# Sheet1.net
KiCad netlist of a schematic drawn in Altium Designer
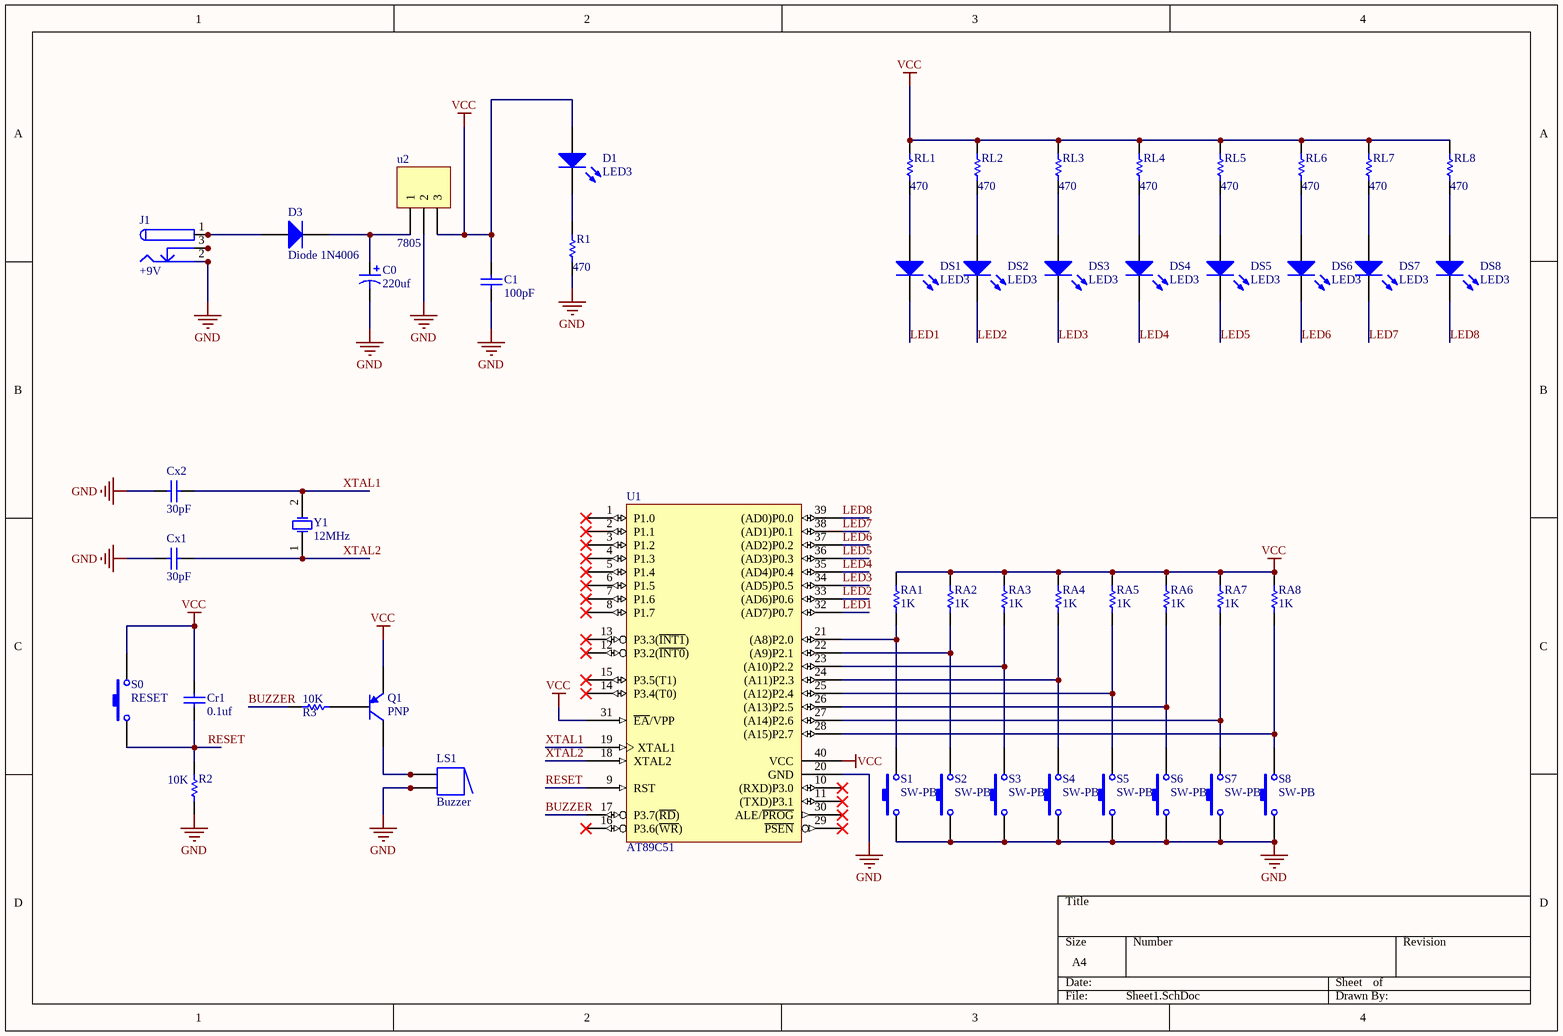
[diagram p0: Sheet1.SchDoc]

(export (version "E")
  (design (tool "Eeschema 10.0.6"))
  (components
    (comp (ref "C0")
      (value "220uf")
      (footprint "RB7.6-15")
      (description "Polarized Capacitor (Radial)")
      (fields (field (name "Comment") "Cap Pol1") (field (name "PUBLISHER") "Altium Limited"))
      (libsource (lib "Chap-11-实践题(3)") (part "Cap Pol1"))
    )
    (comp (ref "C1")
      (value "100pF")
      (footprint "RAD-0.3")
      (description "Capacitor")
      (fields (field (name "Comment") "Cap") (field (name "PUBLISHER") "Altium Limited"))
      (libsource (lib "Chap-11-实践题(3)") (part "Cap"))
    )
    (comp (ref "Cr1")
      (value "0.1uf")
      (footprint "RAD-0.3")
      (description "Capacitor")
      (fields (field (name "Comment") "Cap") (field (name "PUBLISHER") "Altium Limited"))
      (libsource (lib "Chap-11-实践题(3)") (part "Cap"))
    )
    (comp (ref "Cx1")
      (value "30pF")
      (footprint "RAD-0.3")
      (description "Capacitor")
      (fields (field (name "Comment") "Cap") (field (name "PUBLISHER") "Altium Limited"))
      (libsource (lib "Chap-11-实践题(3)") (part "Cap"))
    )
    (comp (ref "Cx2")
      (value "30pF")
      (footprint "RAD-0.3")
      (description "Capacitor")
      (fields (field (name "Comment") "Cap") (field (name "PUBLISHER") "Altium Limited"))
      (libsource (lib "Chap-11-实践题(3)") (part "Cap"))
    )
    (comp (ref "D1")
      (value "LED3")
      (footprint "3.5X2.8X1.9")
      (description "Typical BLUE SiC LED")
      (fields (field (name "PUBLISHER") "Altium Limited"))
      (libsource (lib "Chap-11-实践题(3)") (part "LED3"))
    )
    (comp (ref "D3")
      (value "Diode 1N4006")
      (footprint "DO-41")
      (description "1 Amp General Purpose Rectifier")
      (fields (field (name "PUBLISHER") "Altium Limited"))
      (libsource (lib "Chap-11-实践题(3)") (part "Diode 1N4006"))
    )
    (comp (ref "DS1")
      (value "LED3")
      (footprint "3.5X2.8X1.9")
      (description "Typical BLUE SiC LED")
      (fields (field (name "PUBLISHER") "Altium Limited"))
      (libsource (lib "Chap-11-实践题(3)") (part "LED3"))
    )
    (comp (ref "DS2")
      (value "LED3")
      (footprint "3.5X2.8X1.9")
      (description "Typical BLUE SiC LED")
      (fields (field (name "PUBLISHER") "Altium Limited"))
      (libsource (lib "Chap-11-实践题(3)") (part "LED3"))
    )
    (comp (ref "DS3")
      (value "LED3")
      (footprint "3.5X2.8X1.9")
      (description "Typical BLUE SiC LED")
      (fields (field (name "PUBLISHER") "Altium Limited"))
      (libsource (lib "Chap-11-实践题(3)") (part "LED3"))
    )
    (comp (ref "DS4")
      (value "LED3")
      (footprint "3.5X2.8X1.9")
      (description "Typical BLUE SiC LED")
      (fields (field (name "PUBLISHER") "Altium Limited"))
      (libsource (lib "Chap-11-实践题(3)") (part "LED3"))
    )
    (comp (ref "DS5")
      (value "LED3")
      (footprint "3.5X2.8X1.9")
      (description "Typical BLUE SiC LED")
      (fields (field (name "PUBLISHER") "Altium Limited"))
      (libsource (lib "Chap-11-实践题(3)") (part "LED3"))
    )
    (comp (ref "DS6")
      (value "LED3")
      (footprint "3.5X2.8X1.9")
      (description "Typical BLUE SiC LED")
      (fields (field (name "PUBLISHER") "Altium Limited"))
      (libsource (lib "Chap-11-实践题(3)") (part "LED3"))
    )
    (comp (ref "DS7")
      (value "LED3")
      (footprint "3.5X2.8X1.9")
      (description "Typical BLUE SiC LED")
      (fields (field (name "PUBLISHER") "Altium Limited"))
      (libsource (lib "Chap-11-实践题(3)") (part "LED3"))
    )
    (comp (ref "DS8")
      (value "LED3")
      (footprint "3.5X2.8X1.9")
      (description "Typical BLUE SiC LED")
      (fields (field (name "PUBLISHER") "Altium Limited"))
      (libsource (lib "Chap-11-实践题(3)") (part "LED3"))
    )
    (comp (ref "J1")
      (value "+9V")
      (footprint "KLD-0202")
      (description "Low Voltage Power Supply Connector")
      (fields (field (name "PUBLISHER") "Altium Limited"))
      (libsource (lib "Chap-11-实践题(3)") (part "PWR2.5"))
    )
    (comp (ref "LS1")
      (value "Buzzer")
      (footprint "ABSM-1574")
      (description "Magnetic Transducer Buzzer")
      (fields (field (name "PUBLISHER") "Altium Limited"))
      (libsource (lib "Chap-11-实践题(3)") (part "Buzzer"))
    )
    (comp (ref "Q1")
      (value "PNP")
      (footprint "TO-92A")
      (description "PNP General Purpose Amplifier")
      (fields (field (name "PUBLISHER") "Altium Limited"))
      (libsource (lib "Chap-11-实践题(3)") (part "2N3906"))
    )
    (comp (ref "R1")
      (value "470")
      (footprint "AXIAL-0.3")
      (description "Resistor")
      (fields (field (name "Comment") "Res1") (field (name "PUBLISHER") "Altium Limited"))
      (libsource (lib "Chap-11-实践题(3)") (part "Res1"))
    )
    (comp (ref "R2")
      (value "10K")
      (footprint "AXIAL-0.3")
      (description "Resistor")
      (fields (field (name "Comment") "Res1") (field (name "PUBLISHER") "Altium Limited"))
      (libsource (lib "Chap-11-实践题(3)") (part "Res1"))
    )
    (comp (ref "R3")
      (value "10K")
      (footprint "AXIAL-0.3")
      (description "Resistor")
      (fields (field (name "Comment") "Res1") (field (name "PUBLISHER") "Altium Limited"))
      (libsource (lib "Chap-11-实践题(3)") (part "Res1"))
    )
    (comp (ref "RA1")
      (value "1K")
      (footprint "AXIAL-0.3")
      (description "Resistor")
      (fields (field (name "Comment") "Res1") (field (name "PUBLISHER") "Altium Limited"))
      (libsource (lib "Chap-11-实践题(3)") (part "Res1"))
    )
    (comp (ref "RA2")
      (value "1K")
      (footprint "AXIAL-0.3")
      (description "Resistor")
      (fields (field (name "Comment") "Res1") (field (name "PUBLISHER") "Altium Limited"))
      (libsource (lib "Chap-11-实践题(3)") (part "Res1"))
    )
    (comp (ref "RA3")
      (value "1K")
      (footprint "AXIAL-0.3")
      (description "Resistor")
      (fields (field (name "Comment") "Res1") (field (name "PUBLISHER") "Altium Limited"))
      (libsource (lib "Chap-11-实践题(3)") (part "Res1"))
    )
    (comp (ref "RA4")
      (value "1K")
      (footprint "AXIAL-0.3")
      (description "Resistor")
      (fields (field (name "Comment") "Res1") (field (name "PUBLISHER") "Altium Limited"))
      (libsource (lib "Chap-11-实践题(3)") (part "Res1"))
    )
    (comp (ref "RA5")
      (value "1K")
      (footprint "AXIAL-0.3")
      (description "Resistor")
      (fields (field (name "Comment") "Res1") (field (name "PUBLISHER") "Altium Limited"))
      (libsource (lib "Chap-11-实践题(3)") (part "Res1"))
    )
    (comp (ref "RA6")
      (value "1K")
      (footprint "AXIAL-0.3")
      (description "Resistor")
      (fields (field (name "Comment") "Res1") (field (name "PUBLISHER") "Altium Limited"))
      (libsource (lib "Chap-11-实践题(3)") (part "Res1"))
    )
    (comp (ref "RA7")
      (value "1K")
      (footprint "AXIAL-0.3")
      (description "Resistor")
      (fields (field (name "Comment") "Res1") (field (name "PUBLISHER") "Altium Limited"))
      (libsource (lib "Chap-11-实践题(3)") (part "Res1"))
    )
    (comp (ref "RA8")
      (value "1K")
      (footprint "AXIAL-0.3")
      (description "Resistor")
      (fields (field (name "Comment") "Res1") (field (name "PUBLISHER") "Altium Limited"))
      (libsource (lib "Chap-11-实践题(3)") (part "Res1"))
    )
    (comp (ref "RL1")
      (value "470")
      (footprint "AXIAL-0.3")
      (description "Resistor")
      (fields (field (name "Comment") "Res1") (field (name "PUBLISHER") "Altium Limited"))
      (libsource (lib "Chap-11-实践题(3)") (part "Res1"))
    )
    (comp (ref "RL2")
      (value "470")
      (footprint "AXIAL-0.3")
      (description "Resistor")
      (fields (field (name "Comment") "Res1") (field (name "PUBLISHER") "Altium Limited"))
      (libsource (lib "Chap-11-实践题(3)") (part "Res1"))
    )
    (comp (ref "RL3")
      (value "470")
      (footprint "AXIAL-0.3")
      (description "Resistor")
      (fields (field (name "Comment") "Res1") (field (name "PUBLISHER") "Altium Limited"))
      (libsource (lib "Chap-11-实践题(3)") (part "Res1"))
    )
    (comp (ref "RL4")
      (value "470")
      (footprint "AXIAL-0.3")
      (description "Resistor")
      (fields (field (name "Comment") "Res1") (field (name "PUBLISHER") "Altium Limited"))
      (libsource (lib "Chap-11-实践题(3)") (part "Res1"))
    )
    (comp (ref "RL5")
      (value "470")
      (footprint "AXIAL-0.3")
      (description "Resistor")
      (fields (field (name "Comment") "Res1") (field (name "PUBLISHER") "Altium Limited"))
      (libsource (lib "Chap-11-实践题(3)") (part "Res1"))
    )
    (comp (ref "RL6")
      (value "470")
      (footprint "AXIAL-0.3")
      (description "Resistor")
      (fields (field (name "Comment") "Res1") (field (name "PUBLISHER") "Altium Limited"))
      (libsource (lib "Chap-11-实践题(3)") (part "Res1"))
    )
    (comp (ref "RL7")
      (value "470")
      (footprint "AXIAL-0.3")
      (description "Resistor")
      (fields (field (name "Comment") "Res1") (field (name "PUBLISHER") "Altium Limited"))
      (libsource (lib "Chap-11-实践题(3)") (part "Res1"))
    )
    (comp (ref "RL8")
      (value "470")
      (footprint "AXIAL-0.3")
      (description "Resistor")
      (fields (field (name "Comment") "Res1") (field (name "PUBLISHER") "Altium Limited"))
      (libsource (lib "Chap-11-实践题(3)") (part "Res1"))
    )
    (comp (ref "S0")
      (value "RESET")
      (footprint "SPST-2")
      (description "Switch")
      (fields (field (name "PUBLISHER") "Altium Limited"))
      (libsource (lib "Chap-11-实践题(3)") (part "SW-PB"))
    )
    (comp (ref "S1")
      (value "SW-PB")
      (footprint "SPST-2")
      (description "Switch")
      (fields (field (name "PUBLISHER") "Altium Limited"))
      (libsource (lib "Chap-11-实践题(3)") (part "SW-PB"))
    )
    (comp (ref "S2")
      (value "SW-PB")
      (footprint "SPST-2")
      (description "Switch")
      (fields (field (name "PUBLISHER") "Altium Limited"))
      (libsource (lib "Chap-11-实践题(3)") (part "SW-PB"))
    )
    (comp (ref "S3")
      (value "SW-PB")
      (footprint "SPST-2")
      (description "Switch")
      (fields (field (name "PUBLISHER") "Altium Limited"))
      (libsource (lib "Chap-11-实践题(3)") (part "SW-PB"))
    )
    (comp (ref "S4")
      (value "SW-PB")
      (footprint "SPST-2")
      (description "Switch")
      (fields (field (name "PUBLISHER") "Altium Limited"))
      (libsource (lib "Chap-11-实践题(3)") (part "SW-PB"))
    )
    (comp (ref "S5")
      (value "SW-PB")
      (footprint "SPST-2")
      (description "Switch")
      (fields (field (name "PUBLISHER") "Altium Limited"))
      (libsource (lib "Chap-11-实践题(3)") (part "SW-PB"))
    )
    (comp (ref "S6")
      (value "SW-PB")
      (footprint "SPST-2")
      (description "Switch")
      (fields (field (name "PUBLISHER") "Altium Limited"))
      (libsource (lib "Chap-11-实践题(3)") (part "SW-PB"))
    )
    (comp (ref "S7")
      (value "SW-PB")
      (footprint "SPST-2")
      (description "Switch")
      (fields (field (name "PUBLISHER") "Altium Limited"))
      (libsource (lib "Chap-11-实践题(3)") (part "SW-PB"))
    )
    (comp (ref "S8")
      (value "SW-PB")
      (footprint "SPST-2")
      (description "Switch")
      (fields (field (name "PUBLISHER") "Altium Limited"))
      (libsource (lib "Chap-11-实践题(3)") (part "SW-PB"))
    )
    (comp (ref "U1")
      (value "AT89C51")
      (footprint "DIP-40")
      (description "8-Bit Microcontroller with 4K Flash ROM")
      (libsource (lib "Chap-11-实践题(3)") (part "AT89C51"))
    )
    (comp (ref "u2")
      (value "7805")
      (footprint "HDR1X3H")
      (description "Header, 3-Pin, Right Angle")
      (fields (field (name "PUBLISHER") "Altium Limited"))
      (libsource (lib "Chap-11-实践题(3)") (part "Header 3H"))
    )
    (comp (ref "Y1")
      (value "12MHz")
      (footprint "R38")
      (description "Crystal Oscillator")
      (fields (field (name "PUBLISHER") "Altium Limited"))
      (libsource (lib "Chap-11-实践题(3)") (part "XTAL"))
    )
  )
  (nets
    (net (code "1") (name "/BUZZER") (class "Default")
      (node (ref "R3") (pin "1") (pinfunction "1_1") (pintype "passive"))
      (node (ref "U1") (pin "17") (pinfunction "P3.7(~{RD})_17") (pintype "bidirectional"))
    )
    (net (code "2") (name "/LED1") (class "Default")
      (node (ref "DS1") (pin "2") (pinfunction "K_2") (pintype "passive"))
      (node (ref "U1") (pin "32") (pinfunction "(AD7)P0.7_32") (pintype "bidirectional"))
    )
    (net (code "3") (name "/LED2") (class "Default")
      (node (ref "DS2") (pin "2") (pinfunction "K_2") (pintype "passive"))
      (node (ref "U1") (pin "33") (pinfunction "(AD6)P0.6_33") (pintype "bidirectional"))
    )
    (net (code "4") (name "/LED3") (class "Default")
      (node (ref "DS3") (pin "2") (pinfunction "K_2") (pintype "passive"))
      (node (ref "U1") (pin "34") (pinfunction "(AD5)P0.5_34") (pintype "bidirectional"))
    )
    (net (code "5") (name "/LED4") (class "Default")
      (node (ref "DS4") (pin "2") (pinfunction "K_2") (pintype "passive"))
      (node (ref "U1") (pin "35") (pinfunction "(AD4)P0.4_35") (pintype "bidirectional"))
    )
    (net (code "6") (name "/LED5") (class "Default")
      (node (ref "DS5") (pin "2") (pinfunction "K_2") (pintype "passive"))
      (node (ref "U1") (pin "36") (pinfunction "(AD3)P0.3_36") (pintype "bidirectional"))
    )
    (net (code "7") (name "/LED6") (class "Default")
      (node (ref "DS6") (pin "2") (pinfunction "K_2") (pintype "passive"))
      (node (ref "U1") (pin "37") (pinfunction "(AD2)P0.2_37") (pintype "bidirectional"))
    )
    (net (code "8") (name "/LED7") (class "Default")
      (node (ref "DS7") (pin "2") (pinfunction "K_2") (pintype "passive"))
      (node (ref "U1") (pin "38") (pinfunction "(AD1)P0.1_38") (pintype "bidirectional"))
    )
    (net (code "9") (name "/LED8") (class "Default")
      (node (ref "DS8") (pin "2") (pinfunction "K_2") (pintype "passive"))
      (node (ref "U1") (pin "39") (pinfunction "(AD0)P0.0_39") (pintype "bidirectional"))
    )
    (net (code "10") (name "/RESET") (class "Default")
      (node (ref "Cr1") (pin "1") (pinfunction "1_1") (pintype "passive"))
      (node (ref "R2") (pin "2") (pinfunction "2_2") (pintype "passive"))
      (node (ref "S0") (pin "1") (pinfunction "1_1") (pintype "passive"))
      (node (ref "U1") (pin "9") (pinfunction "RST_9") (pintype "input"))
    )
    (net (code "11") (name "/XTAL1") (class "Default")
      (node (ref "Cx2") (pin "2") (pinfunction "2_2") (pintype "passive"))
      (node (ref "U1") (pin "19") (pinfunction "XTAL1_19") (pintype "input"))
      (node (ref "Y1") (pin "2") (pinfunction "OSC2_2") (pintype "passive"))
    )
    (net (code "12") (name "/XTAL2") (class "Default")
      (node (ref "Cx1") (pin "2") (pinfunction "2_2") (pintype "passive"))
      (node (ref "U1") (pin "18") (pinfunction "XTAL2_18") (pintype "input"))
      (node (ref "Y1") (pin "1") (pinfunction "OSC1_1") (pintype "passive"))
    )
    (net (code "13") (name "GND") (class "Default")
      (node (ref "C0") (pin "2") (pinfunction "2_2") (pintype "passive"))
      (node (ref "C1") (pin "1") (pinfunction "1_1") (pintype "passive"))
      (node (ref "Cx1") (pin "1") (pinfunction "1_1") (pintype "passive"))
      (node (ref "Cx2") (pin "1") (pinfunction "1_1") (pintype "passive"))
      (node (ref "J1") (pin "2") (pinfunction "2_2") (pintype "power_in"))
      (node (ref "J1") (pin "2A") (pinfunction "2A_2A") (pintype "power_in"))
      (node (ref "J1") (pin "2B") (pinfunction "2B_2B") (pintype "power_in"))
      (node (ref "LS1") (pin "2") (pinfunction "2_2") (pintype "passive"))
      (node (ref "LS1") (pin "2A") (pinfunction "2A_2A") (pintype "passive"))
      (node (ref "R1") (pin "1") (pinfunction "1_1") (pintype "passive"))
      (node (ref "R2") (pin "1") (pinfunction "1_1") (pintype "passive"))
      (node (ref "S1") (pin "1") (pinfunction "1_1") (pintype "passive"))
      (node (ref "S2") (pin "1") (pinfunction "1_1") (pintype "passive"))
      (node (ref "S3") (pin "1") (pinfunction "1_1") (pintype "passive"))
      (node (ref "S4") (pin "1") (pinfunction "1_1") (pintype "passive"))
      (node (ref "S5") (pin "1") (pinfunction "1_1") (pintype "passive"))
      (node (ref "S6") (pin "1") (pinfunction "1_1") (pintype "passive"))
      (node (ref "S7") (pin "1") (pinfunction "1_1") (pintype "passive"))
      (node (ref "S8") (pin "1") (pinfunction "1_1") (pintype "passive"))
      (node (ref "U1") (pin "20") (pinfunction "GND_20") (pintype "power_in"))
      (node (ref "u2") (pin "2") (pinfunction "2_2") (pintype "passive"))
    )
    (net (code "14") (name "Net-(D1-K)") (class "Default")
      (node (ref "D1") (pin "2") (pinfunction "K_2") (pintype "passive"))
      (node (ref "R1") (pin "2") (pinfunction "2_2") (pintype "passive"))
    )
    (net (code "15") (name "Net-(D3-A)") (class "Default")
      (node (ref "D3") (pin "1") (pinfunction "A_1") (pintype "passive"))
      (node (ref "J1") (pin "1") (pinfunction "1_1") (pintype "power_in"))
      (node (ref "J1") (pin "1A") (pinfunction "1A_1A") (pintype "power_in"))
      (node (ref "J1") (pin "1B") (pinfunction "1B_1B") (pintype "power_in"))
    )
    (net (code "16") (name "Net-(D3-K)") (class "Default")
      (node (ref "C0") (pin "1") (pinfunction "1_1") (pintype "passive"))
      (node (ref "D3") (pin "2") (pinfunction "K_2") (pintype "passive"))
      (node (ref "u2") (pin "1") (pinfunction "1_1") (pintype "passive"))
    )
    (net (code "17") (name "Net-(DS1-A)") (class "Default")
      (node (ref "DS1") (pin "1") (pinfunction "A_1") (pintype "passive"))
      (node (ref "RL1") (pin "1") (pinfunction "1_1") (pintype "passive"))
    )
    (net (code "18") (name "Net-(DS2-A)") (class "Default")
      (node (ref "DS2") (pin "1") (pinfunction "A_1") (pintype "passive"))
      (node (ref "RL2") (pin "1") (pinfunction "1_1") (pintype "passive"))
    )
    (net (code "19") (name "Net-(DS3-A)") (class "Default")
      (node (ref "DS3") (pin "1") (pinfunction "A_1") (pintype "passive"))
      (node (ref "RL3") (pin "1") (pinfunction "1_1") (pintype "passive"))
    )
    (net (code "20") (name "Net-(DS4-A)") (class "Default")
      (node (ref "DS4") (pin "1") (pinfunction "A_1") (pintype "passive"))
      (node (ref "RL4") (pin "1") (pinfunction "1_1") (pintype "passive"))
    )
    (net (code "21") (name "Net-(DS5-A)") (class "Default")
      (node (ref "DS5") (pin "1") (pinfunction "A_1") (pintype "passive"))
      (node (ref "RL5") (pin "1") (pinfunction "1_1") (pintype "passive"))
    )
    (net (code "22") (name "Net-(DS6-A)") (class "Default")
      (node (ref "DS6") (pin "1") (pinfunction "A_1") (pintype "passive"))
      (node (ref "RL6") (pin "1") (pinfunction "1_1") (pintype "passive"))
    )
    (net (code "23") (name "Net-(DS7-A)") (class "Default")
      (node (ref "DS7") (pin "1") (pinfunction "A_1") (pintype "passive"))
      (node (ref "RL7") (pin "1") (pinfunction "1_1") (pintype "passive"))
    )
    (net (code "24") (name "Net-(DS8-A)") (class "Default")
      (node (ref "DS8") (pin "1") (pinfunction "A_1") (pintype "passive"))
      (node (ref "RL8") (pin "1") (pinfunction "1_1") (pintype "passive"))
    )
    (net (code "25") (name "Net-(J1-Pad3)") (class "Default")
      (node (ref "J1") (pin "3") (pinfunction "3_3") (pintype "power_in"))
      (node (ref "J1") (pin "3A") (pinfunction "3A_3A") (pintype "power_in"))
      (node (ref "J1") (pin "3B") (pinfunction "3B_3B") (pintype "power_in"))
    )
    (net (code "26") (name "Net-(Q1-B)") (class "Default")
      (node (ref "Q1") (pin "2") (pinfunction "B_2") (pintype "passive"))
      (node (ref "R3") (pin "2") (pinfunction "2_2") (pintype "passive"))
    )
    (net (code "27") (name "Net-(Q1-C)") (class "Default")
      (node (ref "LS1") (pin "1") (pinfunction "1_1") (pintype "passive"))
      (node (ref "LS1") (pin "1A") (pinfunction "1A_1A") (pintype "passive"))
      (node (ref "Q1") (pin "3") (pinfunction "C_3") (pintype "passive"))
    )
    (net (code "28") (name "Net-(U1-(A8)P2.0)") (class "Default")
      (node (ref "RA1") (pin "1") (pinfunction "1_1") (pintype "passive"))
      (node (ref "S1") (pin "2") (pinfunction "2_2") (pintype "passive"))
      (node (ref "U1") (pin "21") (pinfunction "(A8)P2.0_21") (pintype "bidirectional"))
    )
    (net (code "29") (name "Net-(U1-(A9)P2.1)") (class "Default")
      (node (ref "RA2") (pin "1") (pinfunction "1_1") (pintype "passive"))
      (node (ref "S2") (pin "2") (pinfunction "2_2") (pintype "passive"))
      (node (ref "U1") (pin "22") (pinfunction "(A9)P2.1_22") (pintype "bidirectional"))
    )
    (net (code "30") (name "Net-(U1-(A10)P2.2)") (class "Default")
      (node (ref "RA3") (pin "1") (pinfunction "1_1") (pintype "passive"))
      (node (ref "S3") (pin "2") (pinfunction "2_2") (pintype "passive"))
      (node (ref "U1") (pin "23") (pinfunction "(A10)P2.2_23") (pintype "bidirectional"))
    )
    (net (code "31") (name "Net-(U1-(A11)P2.3)") (class "Default")
      (node (ref "RA4") (pin "1") (pinfunction "1_1") (pintype "passive"))
      (node (ref "S4") (pin "2") (pinfunction "2_2") (pintype "passive"))
      (node (ref "U1") (pin "24") (pinfunction "(A11)P2.3_24") (pintype "bidirectional"))
    )
    (net (code "32") (name "Net-(U1-(A12)P2.4)") (class "Default")
      (node (ref "RA5") (pin "1") (pinfunction "1_1") (pintype "passive"))
      (node (ref "S5") (pin "2") (pinfunction "2_2") (pintype "passive"))
      (node (ref "U1") (pin "25") (pinfunction "(A12)P2.4_25") (pintype "bidirectional"))
    )
    (net (code "33") (name "Net-(U1-(A13)P2.5)") (class "Default")
      (node (ref "RA6") (pin "1") (pinfunction "1_1") (pintype "passive"))
      (node (ref "S6") (pin "2") (pinfunction "2_2") (pintype "passive"))
      (node (ref "U1") (pin "26") (pinfunction "(A13)P2.5_26") (pintype "bidirectional"))
    )
    (net (code "34") (name "Net-(U1-(A14)P2.6)") (class "Default")
      (node (ref "RA7") (pin "1") (pinfunction "1_1") (pintype "passive"))
      (node (ref "S7") (pin "2") (pinfunction "2_2") (pintype "passive"))
      (node (ref "U1") (pin "27") (pinfunction "(A14)P2.6_27") (pintype "bidirectional"))
    )
    (net (code "35") (name "Net-(U1-(A15)P2.7)") (class "Default")
      (node (ref "RA8") (pin "1") (pinfunction "1_1") (pintype "passive"))
      (node (ref "S8") (pin "2") (pinfunction "2_2") (pintype "passive"))
      (node (ref "U1") (pin "28") (pinfunction "(A15)P2.7_28") (pintype "bidirectional"))
    )
    (net (code "36") (name "VCC") (class "Default")
      (node (ref "C1") (pin "2") (pinfunction "2_2") (pintype "passive"))
      (node (ref "Cr1") (pin "2") (pinfunction "2_2") (pintype "passive"))
      (node (ref "D1") (pin "1") (pinfunction "A_1") (pintype "passive"))
      (node (ref "Q1") (pin "1") (pinfunction "E_1") (pintype "passive"))
      (node (ref "RA1") (pin "2") (pinfunction "2_2") (pintype "passive"))
      (node (ref "RA2") (pin "2") (pinfunction "2_2") (pintype "passive"))
      (node (ref "RA3") (pin "2") (pinfunction "2_2") (pintype "passive"))
      (node (ref "RA4") (pin "2") (pinfunction "2_2") (pintype "passive"))
      (node (ref "RA5") (pin "2") (pinfunction "2_2") (pintype "passive"))
      (node (ref "RA6") (pin "2") (pinfunction "2_2") (pintype "passive"))
      (node (ref "RA7") (pin "2") (pinfunction "2_2") (pintype "passive"))
      (node (ref "RA8") (pin "2") (pinfunction "2_2") (pintype "passive"))
      (node (ref "RL1") (pin "2") (pinfunction "2_2") (pintype "passive"))
      (node (ref "RL2") (pin "2") (pinfunction "2_2") (pintype "passive"))
      (node (ref "RL3") (pin "2") (pinfunction "2_2") (pintype "passive"))
      (node (ref "RL4") (pin "2") (pinfunction "2_2") (pintype "passive"))
      (node (ref "RL5") (pin "2") (pinfunction "2_2") (pintype "passive"))
      (node (ref "RL6") (pin "2") (pinfunction "2_2") (pintype "passive"))
      (node (ref "RL7") (pin "2") (pinfunction "2_2") (pintype "passive"))
      (node (ref "RL8") (pin "2") (pinfunction "2_2") (pintype "passive"))
      (node (ref "S0") (pin "2") (pinfunction "2_2") (pintype "passive"))
      (node (ref "U1") (pin "31") (pinfunction "~{EA}/VPP_31") (pintype "input"))
      (node (ref "U1") (pin "40") (pinfunction "VCC_40") (pintype "power_in"))
      (node (ref "u2") (pin "3") (pinfunction "3_3") (pintype "passive"))
    )
    (net (code "37") (name "unconnected-(U1-(RXD)P3.0-Pad10)") (class "Default")
      (node (ref "U1") (pin "10") (pinfunction "(RXD)P3.0_10") (pintype "bidirectional+no_connect"))
    )
    (net (code "38") (name "unconnected-(U1-(TXD)P3.1-Pad11)") (class "Default")
      (node (ref "U1") (pin "11") (pinfunction "(TXD)P3.1_11") (pintype "bidirectional+no_connect"))
    )
    (net (code "39") (name "unconnected-(U1-ALE{slash}~{PROG}-Pad30)") (class "Default")
      (node (ref "U1") (pin "30") (pinfunction "ALE/~{PROG}_30") (pintype "output+no_connect"))
    )
    (net (code "40") (name "unconnected-(U1-P1.0-Pad1)") (class "Default")
      (node (ref "U1") (pin "1") (pinfunction "P1.0_1") (pintype "bidirectional+no_connect"))
    )
    (net (code "41") (name "unconnected-(U1-P1.1-Pad2)") (class "Default")
      (node (ref "U1") (pin "2") (pinfunction "P1.1_2") (pintype "bidirectional+no_connect"))
    )
    (net (code "42") (name "unconnected-(U1-P1.2-Pad3)") (class "Default")
      (node (ref "U1") (pin "3") (pinfunction "P1.2_3") (pintype "bidirectional+no_connect"))
    )
    (net (code "43") (name "unconnected-(U1-P1.3-Pad4)") (class "Default")
      (node (ref "U1") (pin "4") (pinfunction "P1.3_4") (pintype "bidirectional+no_connect"))
    )
    (net (code "44") (name "unconnected-(U1-P1.4-Pad5)") (class "Default")
      (node (ref "U1") (pin "5") (pinfunction "P1.4_5") (pintype "bidirectional+no_connect"))
    )
    (net (code "45") (name "unconnected-(U1-P1.5-Pad6)") (class "Default")
      (node (ref "U1") (pin "6") (pinfunction "P1.5_6") (pintype "bidirectional+no_connect"))
    )
    (net (code "46") (name "unconnected-(U1-P1.6-Pad7)") (class "Default")
      (node (ref "U1") (pin "7") (pinfunction "P1.6_7") (pintype "bidirectional+no_connect"))
    )
    (net (code "47") (name "unconnected-(U1-P1.7-Pad8)") (class "Default")
      (node (ref "U1") (pin "8") (pinfunction "P1.7_8") (pintype "bidirectional+no_connect"))
    )
    (net (code "48") (name "unconnected-(U1-P3.2(~{INT0})-Pad12)") (class "Default")
      (node (ref "U1") (pin "12") (pinfunction "P3.2(~{INT0})_12") (pintype "bidirectional+no_connect"))
    )
    (net (code "49") (name "unconnected-(U1-P3.3(~{INT1})-Pad13)") (class "Default")
      (node (ref "U1") (pin "13") (pinfunction "P3.3(~{INT1})_13") (pintype "bidirectional+no_connect"))
    )
    (net (code "50") (name "unconnected-(U1-P3.4(T0)-Pad14)") (class "Default")
      (node (ref "U1") (pin "14") (pinfunction "P3.4(T0)_14") (pintype "bidirectional+no_connect"))
    )
    (net (code "51") (name "unconnected-(U1-P3.5(T1)-Pad15)") (class "Default")
      (node (ref "U1") (pin "15") (pinfunction "P3.5(T1)_15") (pintype "bidirectional+no_connect"))
    )
    (net (code "52") (name "unconnected-(U1-P3.6(~{WR})-Pad16)") (class "Default")
      (node (ref "U1") (pin "16") (pinfunction "P3.6(~{WR})_16") (pintype "bidirectional+no_connect"))
    )
    (net (code "53") (name "unconnected-(U1-~{PSEN}-Pad29)") (class "Default")
      (node (ref "U1") (pin "29") (pinfunction "~{PSEN}_29") (pintype "output+no_connect"))
    )
  )
)
